# untitled.net
KiCad netlist of a schematic drawn in EAGLE
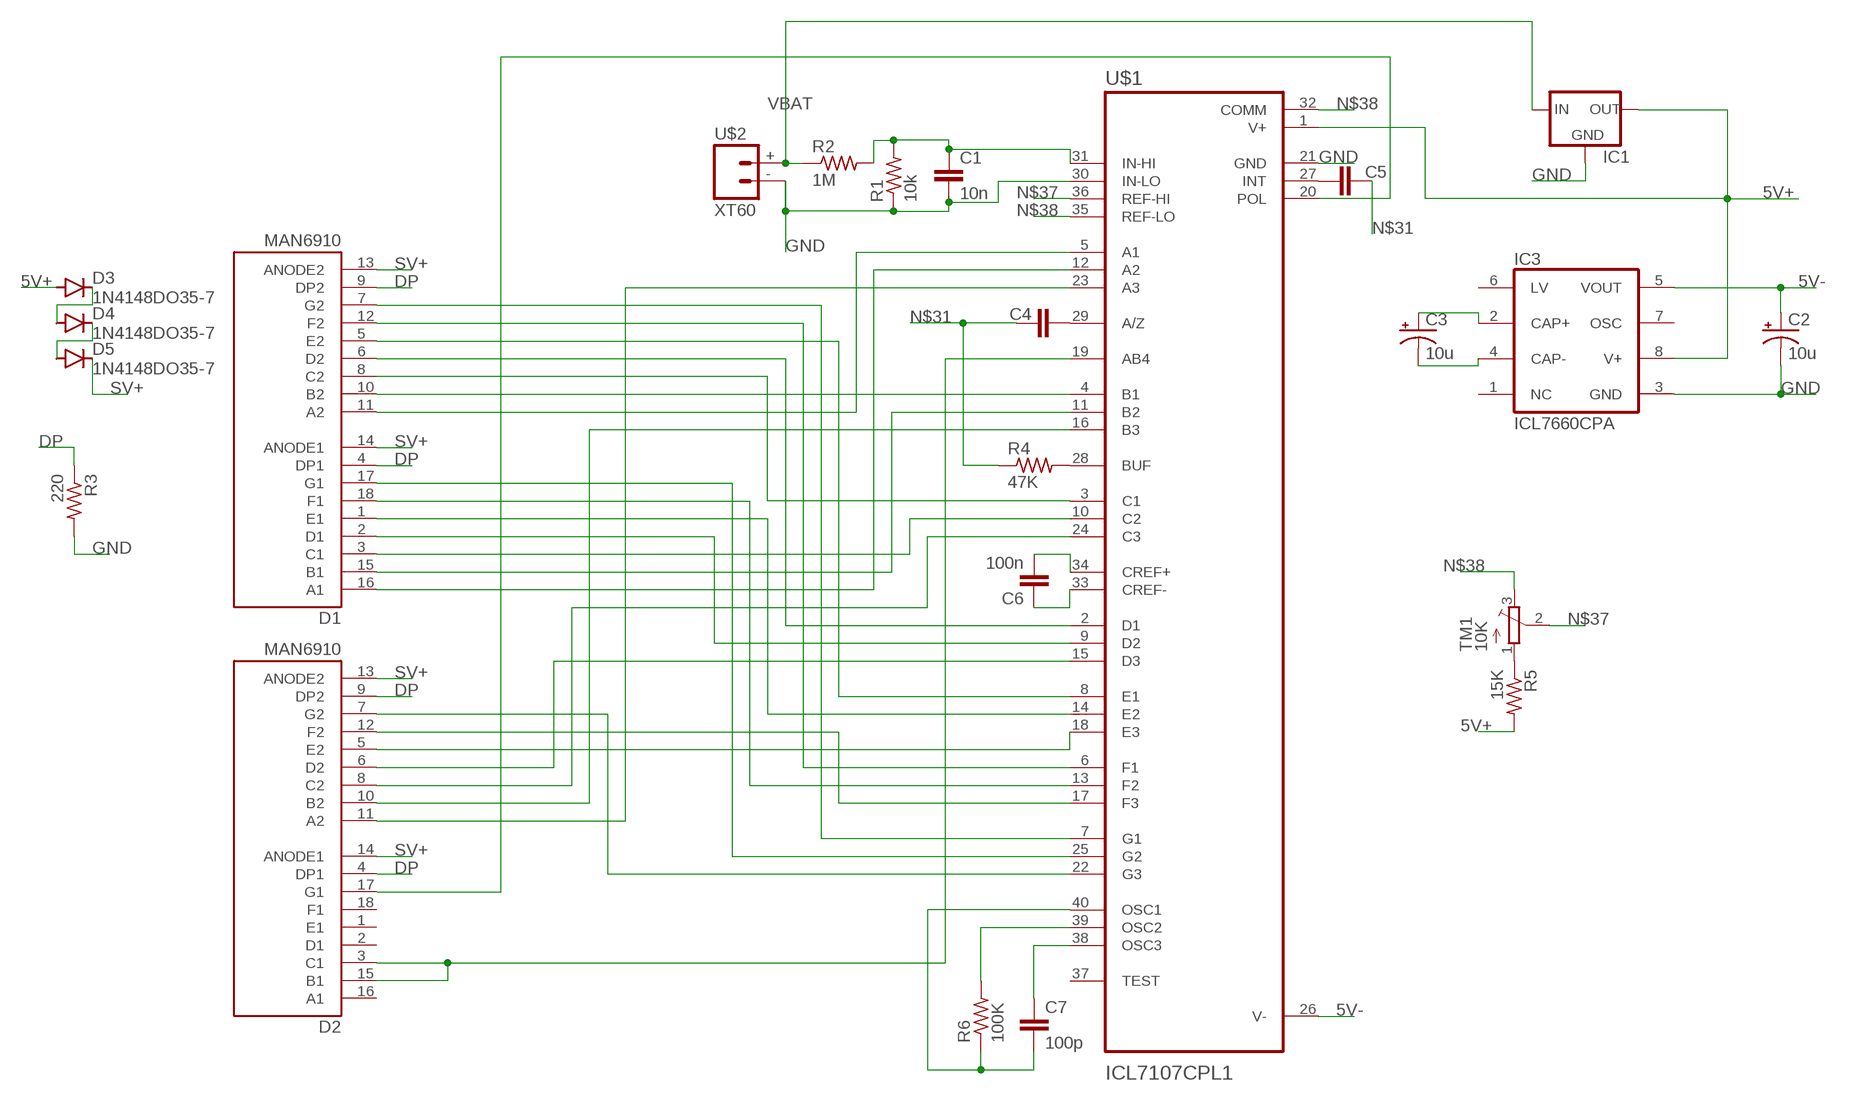
[diagram p0: schematic, sheet 1]

(export (version "E")
  (design (tool "Eeschema 10.0.6"))
  (components
    (comp (ref "C1")
      (value "10n")
      (footprint "eagle-import:CAP-PTH-SMALL-KIT")
      (libsource (lib "eagle-import") (part "CAPKIT"))
    )
    (comp (ref "C2")
      (value "10u")
      (footprint "eagle-import:E2-5")
      (libsource (lib "eagle-import") (part "CAP_THTE2-5"))
    )
    (comp (ref "C3")
      (value "10u")
      (footprint "eagle-import:E2-5")
      (libsource (lib "eagle-import") (part "CAP_THTE2-5"))
    )
    (comp (ref "C4")
      (value "CAPKIT")
      (footprint "eagle-import:CAP-PTH-SMALL-KIT")
      (libsource (lib "eagle-import") (part "CAPKIT"))
    )
    (comp (ref "C5")
      (value "CAPKIT")
      (footprint "eagle-import:CAP-PTH-SMALL-KIT")
      (libsource (lib "eagle-import") (part "CAPKIT"))
    )
    (comp (ref "C6")
      (value "100n")
      (footprint "eagle-import:CAP-PTH-SMALL-KIT")
      (libsource (lib "eagle-import") (part "CAPKIT"))
    )
    (comp (ref "C7")
      (value "100p")
      (footprint "eagle-import:CAP-PTH-SMALL-KIT")
      (libsource (lib "eagle-import") (part "CAPKIT"))
    )
    (comp (ref "D1")
      (value "MAN6910")
      (footprint "eagle-import:DIP1524W51P254L2503H810Q18")
      (fields (field (name "DIGI-KEY_PART_NUMBER") "MAN6910-ND") (field (name "MF") "ON Semiconductor"))
      (libsource (lib "eagle-import") (part "MAN6910"))
    )
    (comp (ref "D2")
      (value "MAN6910")
      (footprint "eagle-import:DIP1524W51P254L2503H810Q18")
      (fields (field (name "DIGI-KEY_PART_NUMBER") "MAN6910-ND") (field (name "MF") "ON Semiconductor"))
      (libsource (lib "eagle-import") (part "MAN6910"))
    )
    (comp (ref "D3")
      (value "1N4148DO35-7")
      (footprint "eagle-import:DO35-7")
      (libsource (lib "eagle-import") (part "1N4148DO35-7"))
    )
    (comp (ref "D4")
      (value "1N4148DO35-7")
      (footprint "eagle-import:DO35-7")
      (libsource (lib "eagle-import") (part "1N4148DO35-7"))
    )
    (comp (ref "D5")
      (value "1N4148DO35-7")
      (footprint "eagle-import:DO35-7")
      (libsource (lib "eagle-import") (part "1N4148DO35-7"))
    )
    (comp (ref "IC1")
      (value "REG_5V_L7805_HOR")
      (footprint "eagle-import:TO-220-H")
      (libsource (lib "eagle-import") (part "REG_5V_L7805_HOR"))
    )
    (comp (ref "IC3")
      (value "ICL7660CPA")
      (footprint "eagle-import:DIL08")
      (fields (field (name "MF") "INTERSIL"))
      (libsource (lib "eagle-import") (part "ICL7660CPA"))
    )
    (comp (ref "R1")
      (value "10k")
      (footprint "eagle-import:1_2W-0.5")
      (libsource (lib "eagle-import") (part "RES_AXIAL1/2W-0.5"))
    )
    (comp (ref "R2")
      (value "1M")
      (footprint "eagle-import:1_2W-0.5")
      (libsource (lib "eagle-import") (part "RES_AXIAL1/2W-0.5"))
    )
    (comp (ref "R3")
      (value "220")
      (footprint "eagle-import:1_2W-0.5")
      (libsource (lib "eagle-import") (part "RES_AXIAL1/2W-0.5"))
    )
    (comp (ref "R4")
      (value "47K")
      (footprint "eagle-import:1_2W-0.5")
      (libsource (lib "eagle-import") (part "RES_AXIAL1/2W-0.5"))
    )
    (comp (ref "R5")
      (value "15K")
      (footprint "eagle-import:1_2W-0.5")
      (libsource (lib "eagle-import") (part "RES_AXIAL1/2W-0.5"))
    )
    (comp (ref "R6")
      (value "100K")
      (footprint "eagle-import:1_2W-0.5")
      (libsource (lib "eagle-import") (part "RES_AXIAL1/2W-0.5"))
    )
    (comp (ref "TM1")
      (value "10K")
      (footprint "eagle-import:TC33X")
      (libsource (lib "eagle-import") (part "TRIMPOTTC33X"))
    )
    (comp (ref "U$1")
      (value "ICL7107CPL1")
      (footprint "eagle-import:DIP1524W46P254L5271H508Q40")
      (fields
        (field (name "DIGI-KEY_PART_NUMBER") "ICL7107CPL-ND")
        (field (name "MF") "Maxim Integrated")
        (field (name "MP") "ICL7107CPL")
      )
      (libsource (lib "eagle-import") (part "ICL7107CPL1"))
    )
    (comp (ref "U$2")
      (value "XT60")
      (footprint "eagle-import:XT60")
      (libsource (lib "eagle-import") (part "XT60"))
    )
  )
  (nets
    (net (code "1") (name "/5V+") (class "Default")
      (node (ref "D3") (pin "A") (pinfunction "A_A") (pintype "passive"))
      (node (ref "IC1") (pin "3") (pinfunction "OUT_3") (pintype "output"))
      (node (ref "IC3") (pin "8") (pinfunction "V+_8") (pintype "power_in"))
      (node (ref "R5") (pin "2") (pinfunction "2_2") (pintype "passive"))
      (node (ref "U$1") (pin "1") (pinfunction "V+_1") (pintype "power_in"))
    )
    (net (code "2") (name "/5V-") (class "Default")
      (node (ref "C2") (pin "+") (pinfunction "+_+") (pintype "passive"))
      (node (ref "IC3") (pin "5") (pinfunction "VOUT_5") (pintype "output"))
      (node (ref "U$1") (pin "26") (pinfunction "V-_26") (pintype "power_in"))
    )
    (net (code "3") (name "/DP") (class "Default")
      (node (ref "D1") (pin "4") (pinfunction "DP1_4") (pintype "passive"))
      (node (ref "D1") (pin "9") (pinfunction "DP2_9") (pintype "passive"))
      (node (ref "D2") (pin "4") (pinfunction "DP1_4") (pintype "passive"))
      (node (ref "D2") (pin "9") (pinfunction "DP2_9") (pintype "passive"))
      (node (ref "R3") (pin "1") (pinfunction "1_1") (pintype "passive"))
    )
    (net (code "4") (name "/GND") (class "Default")
      (node (ref "C1") (pin "2") (pinfunction "2_2") (pintype "passive"))
      (node (ref "C2") (pin "-") (pinfunction "-_-") (pintype "passive"))
      (node (ref "IC1") (pin "2") (pinfunction "GND_2") (pintype "input"))
      (node (ref "IC3") (pin "3") (pinfunction "GND_3") (pintype "power_in"))
      (node (ref "R1") (pin "1") (pinfunction "1_1") (pintype "passive"))
      (node (ref "R3") (pin "2") (pinfunction "2_2") (pintype "passive"))
      (node (ref "U$1") (pin "21") (pinfunction "GND_21") (pintype "output"))
      (node (ref "U$1") (pin "30") (pinfunction "IN-LO_30") (pintype "input"))
      (node (ref "U$2") (pin "-") (pinfunction "1_-") (pintype "passive"))
    )
    (net (code "5") (name "/N$31") (class "Default")
      (node (ref "C4") (pin "2") (pinfunction "2_2") (pintype "passive"))
      (node (ref "C5") (pin "1") (pinfunction "1_1") (pintype "passive"))
      (node (ref "R4") (pin "1") (pinfunction "1_1") (pintype "passive"))
    )
    (net (code "6") (name "/N$37") (class "Default")
      (node (ref "TM1") (pin "2") (pinfunction "S_2") (pintype "passive"))
      (node (ref "U$1") (pin "36") (pinfunction "REF-HI_36") (pintype "input"))
    )
    (net (code "7") (name "/N$38") (class "Default")
      (node (ref "TM1") (pin "3") (pinfunction "E_3") (pintype "passive"))
      (node (ref "U$1") (pin "32") (pinfunction "COMM_32") (pintype "power_in"))
      (node (ref "U$1") (pin "35") (pinfunction "REF-LO_35") (pintype "input"))
    )
    (net (code "8") (name "/SV+") (class "Default")
      (node (ref "D1") (pin "13") (pinfunction "ANODE2_13") (pintype "passive"))
      (node (ref "D1") (pin "14") (pinfunction "ANODE1_14") (pintype "passive"))
      (node (ref "D2") (pin "13") (pinfunction "ANODE2_13") (pintype "passive"))
      (node (ref "D2") (pin "14") (pinfunction "ANODE1_14") (pintype "passive"))
      (node (ref "D5") (pin "C") (pinfunction "C_C") (pintype "passive"))
    )
    (net (code "9") (name "/VBAT") (class "Default")
      (node (ref "IC1") (pin "1") (pinfunction "IN_1") (pintype "input"))
      (node (ref "R2") (pin "1") (pinfunction "1_1") (pintype "passive"))
      (node (ref "U$2") (pin "+") (pinfunction "2_+") (pintype "passive"))
    )
    (net (code "10") (name "Net-(D1-A1)") (class "Default")
      (node (ref "D1") (pin "16") (pinfunction "A1_16") (pintype "passive"))
      (node (ref "U$1") (pin "12") (pinfunction "A2_12") (pintype "bidirectional"))
    )
    (net (code "11") (name "Net-(D1-A2)") (class "Default")
      (node (ref "D1") (pin "11") (pinfunction "A2_11") (pintype "passive"))
      (node (ref "U$1") (pin "5") (pinfunction "A1_5") (pintype "bidirectional"))
    )
    (net (code "12") (name "Net-(D1-B1)") (class "Default")
      (node (ref "D1") (pin "15") (pinfunction "B1_15") (pintype "passive"))
      (node (ref "U$1") (pin "11") (pinfunction "B2_11") (pintype "bidirectional"))
    )
    (net (code "13") (name "Net-(D1-B2)") (class "Default")
      (node (ref "D1") (pin "10") (pinfunction "B2_10") (pintype "passive"))
      (node (ref "U$1") (pin "4") (pinfunction "B1_4") (pintype "bidirectional"))
    )
    (net (code "14") (name "Net-(D1-C1)") (class "Default")
      (node (ref "D1") (pin "3") (pinfunction "C1_3") (pintype "passive"))
      (node (ref "U$1") (pin "10") (pinfunction "C2_10") (pintype "bidirectional"))
    )
    (net (code "15") (name "Net-(D1-C2)") (class "Default")
      (node (ref "D1") (pin "8") (pinfunction "C2_8") (pintype "passive"))
      (node (ref "U$1") (pin "3") (pinfunction "C1_3") (pintype "bidirectional"))
    )
    (net (code "16") (name "Net-(D1-D1)") (class "Default")
      (node (ref "D1") (pin "2") (pinfunction "D1_2") (pintype "passive"))
      (node (ref "U$1") (pin "9") (pinfunction "D2_9") (pintype "bidirectional"))
    )
    (net (code "17") (name "Net-(D1-D2)") (class "Default")
      (node (ref "D1") (pin "6") (pinfunction "D2_6") (pintype "passive"))
      (node (ref "U$1") (pin "2") (pinfunction "D1_2") (pintype "bidirectional"))
    )
    (net (code "18") (name "Net-(D1-E1)") (class "Default")
      (node (ref "D1") (pin "1") (pinfunction "E1_1") (pintype "passive"))
      (node (ref "U$1") (pin "14") (pinfunction "E2_14") (pintype "bidirectional"))
    )
    (net (code "19") (name "Net-(D1-E2)") (class "Default")
      (node (ref "D1") (pin "5") (pinfunction "E2_5") (pintype "passive"))
      (node (ref "U$1") (pin "8") (pinfunction "E1_8") (pintype "bidirectional"))
    )
    (net (code "20") (name "Net-(D1-F1)") (class "Default")
      (node (ref "D1") (pin "18") (pinfunction "F1_18") (pintype "passive"))
      (node (ref "U$1") (pin "13") (pinfunction "F2_13") (pintype "bidirectional"))
    )
    (net (code "21") (name "Net-(D1-F2)") (class "Default")
      (node (ref "D1") (pin "12") (pinfunction "F2_12") (pintype "passive"))
      (node (ref "U$1") (pin "6") (pinfunction "F1_6") (pintype "bidirectional"))
    )
    (net (code "22") (name "Net-(D1-G1)") (class "Default")
      (node (ref "D1") (pin "17") (pinfunction "G1_17") (pintype "passive"))
      (node (ref "U$1") (pin "25") (pinfunction "G2_25") (pintype "bidirectional"))
    )
    (net (code "23") (name "Net-(D1-G2)") (class "Default")
      (node (ref "D1") (pin "7") (pinfunction "G2_7") (pintype "passive"))
      (node (ref "U$1") (pin "7") (pinfunction "G1_7") (pintype "bidirectional"))
    )
    (net (code "24") (name "Net-(D2-A2)") (class "Default")
      (node (ref "D2") (pin "11") (pinfunction "A2_11") (pintype "passive"))
      (node (ref "U$1") (pin "23") (pinfunction "A3_23") (pintype "bidirectional"))
    )
    (net (code "25") (name "Net-(D2-B1)") (class "Default")
      (node (ref "D2") (pin "15") (pinfunction "B1_15") (pintype "passive"))
      (node (ref "D2") (pin "3") (pinfunction "C1_3") (pintype "passive"))
      (node (ref "U$1") (pin "19") (pinfunction "AB4_19") (pintype "bidirectional"))
    )
    (net (code "26") (name "Net-(D2-B2)") (class "Default")
      (node (ref "D2") (pin "10") (pinfunction "B2_10") (pintype "passive"))
      (node (ref "U$1") (pin "16") (pinfunction "B3_16") (pintype "bidirectional"))
    )
    (net (code "27") (name "Net-(D2-C2)") (class "Default")
      (node (ref "D2") (pin "8") (pinfunction "C2_8") (pintype "passive"))
      (node (ref "U$1") (pin "24") (pinfunction "C3_24") (pintype "bidirectional"))
    )
    (net (code "28") (name "Net-(D2-D2)") (class "Default")
      (node (ref "D2") (pin "6") (pinfunction "D2_6") (pintype "passive"))
      (node (ref "U$1") (pin "15") (pinfunction "D3_15") (pintype "bidirectional"))
    )
    (net (code "29") (name "Net-(D2-E2)") (class "Default")
      (node (ref "D2") (pin "5") (pinfunction "E2_5") (pintype "passive"))
      (node (ref "U$1") (pin "18") (pinfunction "E3_18") (pintype "bidirectional"))
    )
    (net (code "30") (name "Net-(D2-F2)") (class "Default")
      (node (ref "D2") (pin "12") (pinfunction "F2_12") (pintype "passive"))
      (node (ref "U$1") (pin "17") (pinfunction "F3_17") (pintype "bidirectional"))
    )
    (net (code "31") (name "Net-(D2-G1)") (class "Default")
      (node (ref "D2") (pin "17") (pinfunction "G1_17") (pintype "passive"))
      (node (ref "U$1") (pin "20") (pinfunction "POL_20") (pintype "output"))
    )
    (net (code "32") (name "Net-(D2-G2)") (class "Default")
      (node (ref "D2") (pin "7") (pinfunction "G2_7") (pintype "passive"))
      (node (ref "U$1") (pin "22") (pinfunction "G3_22") (pintype "bidirectional"))
    )
    (net (code "33") (name "Net-(D3-PadC)") (class "Default")
      (node (ref "D3") (pin "C") (pinfunction "C_C") (pintype "passive"))
      (node (ref "D4") (pin "A") (pinfunction "A_A") (pintype "passive"))
    )
    (net (code "34") (name "Net-(D4-PadC)") (class "Default")
      (node (ref "D4") (pin "C") (pinfunction "C_C") (pintype "passive"))
      (node (ref "D5") (pin "A") (pinfunction "A_A") (pintype "passive"))
    )
    (net (code "35") (name "Net-(IC3-CAP+)") (class "Default")
      (node (ref "C3") (pin "+") (pinfunction "+_+") (pintype "passive"))
      (node (ref "IC3") (pin "2") (pinfunction "CAP+_2") (pintype "passive"))
    )
    (net (code "36") (name "Net-(IC3-CAP-)") (class "Default")
      (node (ref "C3") (pin "-") (pinfunction "-_-") (pintype "passive"))
      (node (ref "IC3") (pin "4") (pinfunction "CAP-_4") (pintype "passive"))
    )
    (net (code "37") (name "Net-(TM1-A)") (class "Default")
      (node (ref "R5") (pin "1") (pinfunction "1_1") (pintype "passive"))
      (node (ref "TM1") (pin "1") (pinfunction "A_1") (pintype "passive"))
    )
    (net (code "38") (name "Net-(U$1-A{slash}Z)") (class "Default")
      (node (ref "C4") (pin "1") (pinfunction "1_1") (pintype "passive"))
      (node (ref "U$1") (pin "29") (pinfunction "A/Z_29") (pintype "bidirectional"))
    )
    (net (code "39") (name "Net-(U$1-BUF)") (class "Default")
      (node (ref "R4") (pin "2") (pinfunction "2_2") (pintype "passive"))
      (node (ref "U$1") (pin "28") (pinfunction "BUF_28") (pintype "bidirectional"))
    )
    (net (code "40") (name "Net-(U$1-CREF+)") (class "Default")
      (node (ref "C6") (pin "2") (pinfunction "2_2") (pintype "passive"))
      (node (ref "U$1") (pin "34") (pinfunction "CREF+_34") (pintype "bidirectional"))
    )
    (net (code "41") (name "Net-(U$1-CREF-)") (class "Default")
      (node (ref "C6") (pin "1") (pinfunction "1_1") (pintype "passive"))
      (node (ref "U$1") (pin "33") (pinfunction "CREF-_33") (pintype "bidirectional"))
    )
    (net (code "42") (name "Net-(U$1-IN-HI)") (class "Default")
      (node (ref "C1") (pin "1") (pinfunction "1_1") (pintype "passive"))
      (node (ref "R1") (pin "2") (pinfunction "2_2") (pintype "passive"))
      (node (ref "R2") (pin "2") (pinfunction "2_2") (pintype "passive"))
      (node (ref "U$1") (pin "31") (pinfunction "IN-HI_31") (pintype "input"))
    )
    (net (code "43") (name "Net-(U$1-INT)") (class "Default")
      (node (ref "C5") (pin "2") (pinfunction "2_2") (pintype "passive"))
      (node (ref "U$1") (pin "27") (pinfunction "INT_27") (pintype "output"))
    )
    (net (code "44") (name "Net-(U$1-OSC1)") (class "Default")
      (node (ref "C7") (pin "2") (pinfunction "2_2") (pintype "passive"))
      (node (ref "R6") (pin "1") (pinfunction "1_1") (pintype "passive"))
      (node (ref "U$1") (pin "40") (pinfunction "OSC1_40") (pintype "bidirectional"))
    )
    (net (code "45") (name "Net-(U$1-OSC2)") (class "Default")
      (node (ref "R6") (pin "2") (pinfunction "2_2") (pintype "passive"))
      (node (ref "U$1") (pin "39") (pinfunction "OSC2_39") (pintype "bidirectional"))
    )
    (net (code "46") (name "Net-(U$1-OSC3)") (class "Default")
      (node (ref "C7") (pin "1") (pinfunction "1_1") (pintype "passive"))
      (node (ref "U$1") (pin "38") (pinfunction "OSC3_38") (pintype "bidirectional"))
    )
    (net (code "47") (name "unconnected-(D2-A1-Pad16)") (class "Default")
      (node (ref "D2") (pin "16") (pinfunction "A1_16") (pintype "passive"))
    )
    (net (code "48") (name "unconnected-(D2-D1-Pad2)") (class "Default")
      (node (ref "D2") (pin "2") (pinfunction "D1_2") (pintype "passive"))
    )
    (net (code "49") (name "unconnected-(D2-E1-Pad1)") (class "Default")
      (node (ref "D2") (pin "1") (pinfunction "E1_1") (pintype "passive"))
    )
    (net (code "50") (name "unconnected-(D2-F1-Pad18)") (class "Default")
      (node (ref "D2") (pin "18") (pinfunction "F1_18") (pintype "passive"))
    )
    (net (code "51") (name "unconnected-(IC3-LV-Pad6)") (class "Default")
      (node (ref "IC3") (pin "6") (pinfunction "LV_6") (pintype "passive"))
    )
    (net (code "52") (name "unconnected-(IC3-NC-Pad1)") (class "Default")
      (node (ref "IC3") (pin "1") (pinfunction "NC_1") (pintype "no_connect"))
    )
    (net (code "53") (name "unconnected-(IC3-OSC-Pad7)") (class "Default")
      (node (ref "IC3") (pin "7") (pinfunction "OSC_7") (pintype "output"))
    )
    (net (code "54") (name "unconnected-(U$1-TEST-Pad37)") (class "Default")
      (node (ref "U$1") (pin "37") (pinfunction "TEST_37") (pintype "bidirectional"))
    )
  )
)
